# regdualsupply.net
KiCad netlist of a schematic drawn in EAGLE
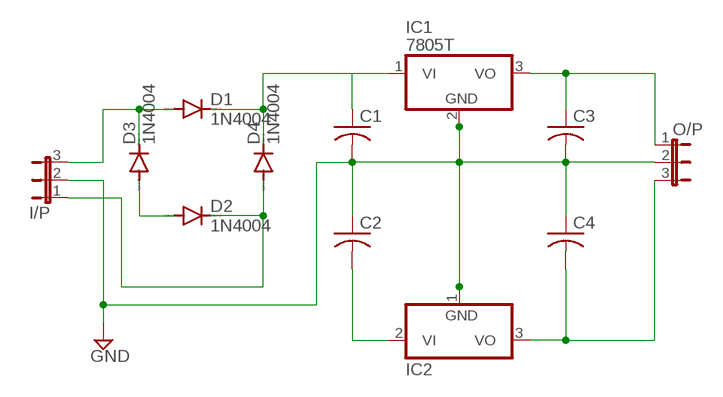
[diagram p0: schematic, sheet 1]

(export (version "E")
  (design (tool "Eeschema 10.0.6"))
  (components
    (comp (ref "C1")
      (value "C-US025-025X050")
      (footprint "eagle-import:C025-025X050")
      (libsource (lib "eagle-import") (part "C-US025-025X050"))
    )
    (comp (ref "C2")
      (value "C-US025-025X050")
      (footprint "eagle-import:C025-025X050")
      (libsource (lib "eagle-import") (part "C-US025-025X050"))
    )
    (comp (ref "C3")
      (value "C-US025-025X050")
      (footprint "eagle-import:C025-025X050")
      (libsource (lib "eagle-import") (part "C-US025-025X050"))
    )
    (comp (ref "C4")
      (value "C-US025-025X050")
      (footprint "eagle-import:C025-025X050")
      (libsource (lib "eagle-import") (part "C-US025-025X050"))
    )
    (comp (ref "D1")
      (value "1N4004")
      (footprint "eagle-import:DO41-10")
      (libsource (lib "eagle-import") (part "1N4004"))
    )
    (comp (ref "D2")
      (value "1N4004")
      (footprint "eagle-import:DO41-10")
      (libsource (lib "eagle-import") (part "1N4004"))
    )
    (comp (ref "D3")
      (value "1N4004")
      (footprint "eagle-import:DO41-10")
      (libsource (lib "eagle-import") (part "1N4004"))
    )
    (comp (ref "D4")
      (value "1N4004")
      (footprint "eagle-import:DO41-10")
      (libsource (lib "eagle-import") (part "1N4004"))
    )
    (comp (ref "I/P")
      (value "JP2W")
      (footprint "eagle-import:JP2W")
      (libsource (lib "eagle-import") (part "JP2W"))
    )
    (comp (ref "IC1")
      (value "7805T")
      (footprint "eagle-import:TO220H")
      (libsource (lib "eagle-import") (part "78T05"))
    )
    (comp (ref "IC2")
      (value "7905T")
      (footprint "eagle-import:TO220H")
      (libsource (lib "eagle-import") (part "79T05"))
    )
    (comp (ref "O/P")
      (value "JP2W")
      (footprint "eagle-import:JP2W")
      (libsource (lib "eagle-import") (part "JP2W"))
    )
  )
  (nets
    (net (code "1") (name "GND") (class "Default")
      (node (ref "C1") (pin "2") (pinfunction "2_2") (pintype "passive"))
      (node (ref "C2") (pin "1") (pinfunction "1_1") (pintype "passive"))
      (node (ref "C3") (pin "2") (pinfunction "2_2") (pintype "passive"))
      (node (ref "C4") (pin "1") (pinfunction "1_1") (pintype "passive"))
      (node (ref "I/P") (pin "2") (pinfunction "2_2") (pintype "passive"))
      (node (ref "IC1") (pin "2") (pinfunction "GND_2") (pintype "passive"))
      (node (ref "IC2") (pin "1") (pinfunction "GND_1") (pintype "passive"))
      (node (ref "O/P") (pin "2") (pinfunction "2_2") (pintype "passive"))
    )
    (net (code "2") (name "Net-(D1-PadA)") (class "Default")
      (node (ref "D1") (pin "A") (pinfunction "A_A") (pintype "passive"))
      (node (ref "D3") (pin "C") (pinfunction "C_C") (pintype "passive"))
      (node (ref "I/P") (pin "3") (pinfunction "3_3") (pintype "passive"))
    )
    (net (code "3") (name "Net-(D2-PadA)") (class "Default")
      (node (ref "D2") (pin "A") (pinfunction "A_A") (pintype "passive"))
      (node (ref "D3") (pin "A") (pinfunction "A_A") (pintype "passive"))
    )
    (net (code "4") (name "Net-(D2-PadC)") (class "Default")
      (node (ref "D2") (pin "C") (pinfunction "C_C") (pintype "passive"))
      (node (ref "D4") (pin "A") (pinfunction "A_A") (pintype "passive"))
      (node (ref "I/P") (pin "1") (pinfunction "1_1") (pintype "passive"))
    )
    (net (code "5") (name "Net-(IC1-VI)") (class "Default")
      (node (ref "C1") (pin "1") (pinfunction "1_1") (pintype "passive"))
      (node (ref "D1") (pin "C") (pinfunction "C_C") (pintype "passive"))
      (node (ref "D4") (pin "C") (pinfunction "C_C") (pintype "passive"))
      (node (ref "IC1") (pin "1") (pinfunction "VI_1") (pintype "input"))
    )
    (net (code "6") (name "Net-(IC1-VO)") (class "Default")
      (node (ref "C3") (pin "1") (pinfunction "1_1") (pintype "passive"))
      (node (ref "IC1") (pin "3") (pinfunction "VO_3") (pintype "passive"))
      (node (ref "O/P") (pin "1") (pinfunction "1_1") (pintype "passive"))
    )
    (net (code "7") (name "Net-(IC2-VI)") (class "Default")
      (node (ref "C2") (pin "2") (pinfunction "2_2") (pintype "passive"))
      (node (ref "IC2") (pin "2") (pinfunction "VI_2") (pintype "input"))
    )
    (net (code "8") (name "Net-(IC2-VO)") (class "Default")
      (node (ref "C4") (pin "2") (pinfunction "2_2") (pintype "passive"))
      (node (ref "IC2") (pin "3") (pinfunction "VO_3") (pintype "passive"))
      (node (ref "O/P") (pin "3") (pinfunction "3_3") (pintype "passive"))
    )
  )
)
